# molecule-io.net
KiCad netlist of a schematic drawn in EAGLE
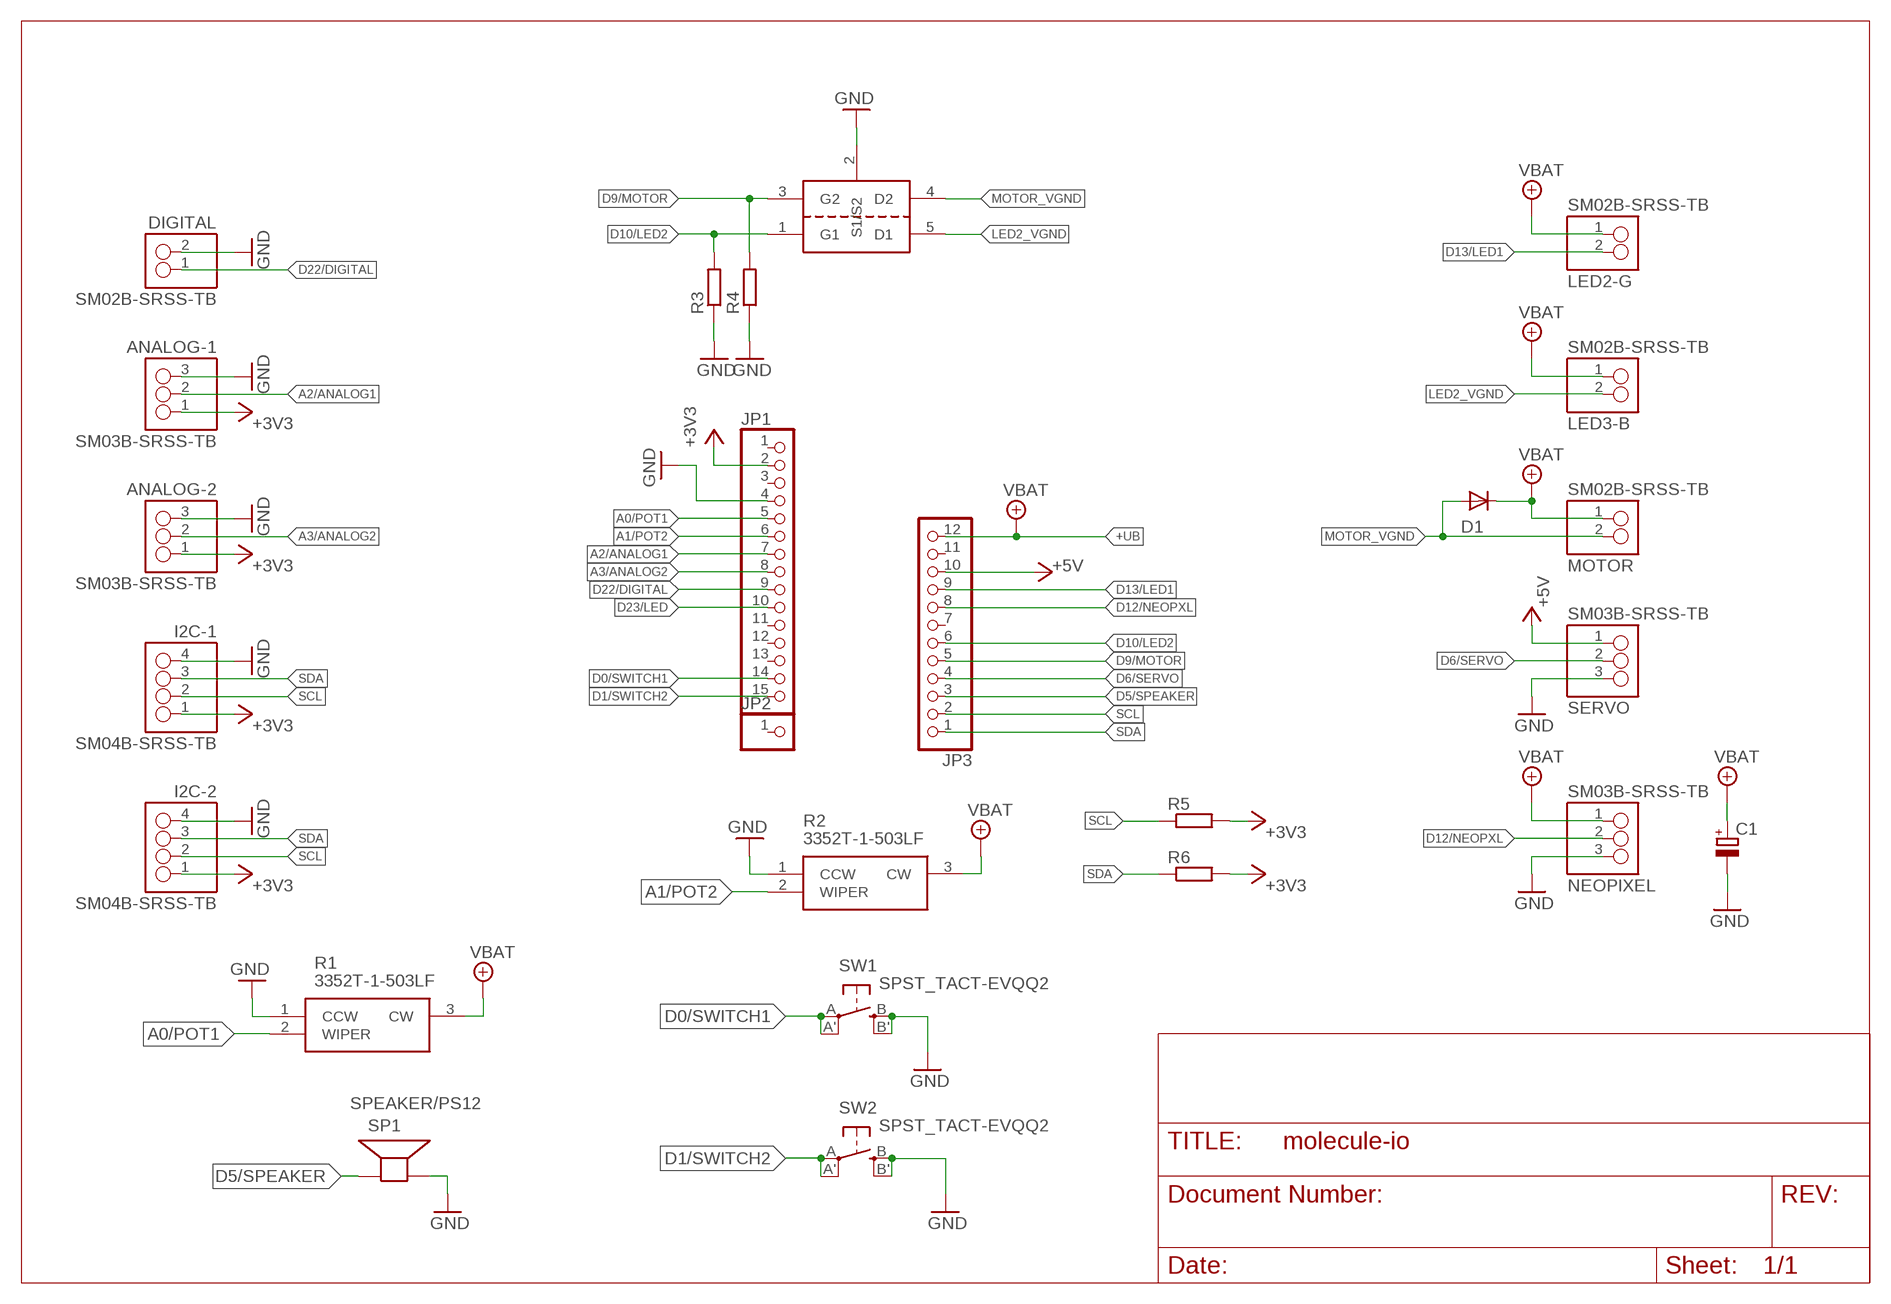
[diagram p0: schematic, sheet 1]

(export (version "E")
  (design (tool "Eeschema 10.0.6"))
  (components
    (comp (ref "ANALOG-1")
      (value "SM03B-SRSS-TB")
      (footprint "eagle-import:SM03B-SRSS-TB")
      (libsource (lib "eagle-import") (part "SM03B-SRSS-TB"))
    )
    (comp (ref "ANALOG-2")
      (value "SM03B-SRSS-TB")
      (footprint "eagle-import:SM03B-SRSS-TB")
      (libsource (lib "eagle-import") (part "SM03B-SRSS-TB"))
    )
    (comp (ref "C1")
      (value "CPOL-EUD")
      (footprint "eagle-import:PANASONIC_D")
      (libsource (lib "eagle-import") (part "CPOL-EUD"))
    )
    (comp (ref "D1")
      (value "DIODE-DO-214AC")
      (footprint "eagle-import:DO-214AC")
      (libsource (lib "eagle-import") (part "DIODE-DO-214AC"))
    )
    (comp (ref "DIGITAL")
      (value "SM02B-SRSS-TB")
      (footprint "eagle-import:SM02B-SRSS-TB")
      (libsource (lib "eagle-import") (part "SM02B-SRSS-TB"))
    )
    (comp (ref "I2C-1")
      (value "SM04B-SRSS-TB")
      (footprint "eagle-import:SM04B-SRSS-TB")
      (libsource (lib "eagle-import") (part "SM04B-SRSS-TB"))
    )
    (comp (ref "I2C-2")
      (value "SM04B-SRSS-TB")
      (footprint "eagle-import:SM04B-SRSS-TB")
      (libsource (lib "eagle-import") (part "SM04B-SRSS-TB"))
    )
    (comp (ref "JP1")
      (value "PINHD-1X15-CB")
      (footprint "eagle-import:1X15-CB")
      (libsource (lib "eagle-import") (part "PINHD-1X15-CB"))
    )
    (comp (ref "JP2")
      (value "PINHD-1X1CB")
      (footprint "eagle-import:1X01-CLEANBIG")
      (libsource (lib "eagle-import") (part "PINHD-1X1CB"))
    )
    (comp (ref "JP3")
      (value "PINHD-1X12-CB")
      (footprint "eagle-import:1X12-CB")
      (libsource (lib "eagle-import") (part "PINHD-1X12-CB"))
    )
    (comp (ref "LED2-G")
      (value "SM02B-SRSS-TB")
      (footprint "eagle-import:SM02B-SRSS-TB")
      (libsource (lib "eagle-import") (part "SM02B-SRSS-TB"))
    )
    (comp (ref "LED3-B")
      (value "SM02B-SRSS-TB")
      (footprint "eagle-import:SM02B-SRSS-TB")
      (libsource (lib "eagle-import") (part "SM02B-SRSS-TB"))
    )
    (comp (ref "MOTOR")
      (value "SM02B-SRSS-TB")
      (footprint "eagle-import:SM02B-SRSS-TB")
      (libsource (lib "eagle-import") (part "SM02B-SRSS-TB"))
    )
    (comp (ref "NEOPIXEL")
      (value "SM03B-SRSS-TB")
      (footprint "eagle-import:SM03B-SRSS-TB")
      (libsource (lib "eagle-import") (part "SM03B-SRSS-TB"))
    )
    (comp (ref "R1")
      (value "3352T-1-503LF")
      (footprint "eagle-import:3352T")
      (libsource (lib "eagle-import") (part "3352T-1-503LF"))
    )
    (comp (ref "R2")
      (value "3352T-1-503LF")
      (footprint "eagle-import:3352T")
      (libsource (lib "eagle-import") (part "3352T-1-503LF"))
    )
    (comp (ref "R3")
      (value "R-EU_R0603")
      (footprint "eagle-import:R0603")
      (libsource (lib "eagle-import") (part "R-EU_R0603"))
    )
    (comp (ref "R4")
      (value "R-EU_R0603")
      (footprint "eagle-import:R0603")
      (libsource (lib "eagle-import") (part "R-EU_R0603"))
    )
    (comp (ref "R5")
      (value "R-EU_R0603")
      (footprint "eagle-import:R0603")
      (libsource (lib "eagle-import") (part "R-EU_R0603"))
    )
    (comp (ref "R6")
      (value "R-EU_R0603")
      (footprint "eagle-import:R0603")
      (libsource (lib "eagle-import") (part "R-EU_R0603"))
    )
    (comp (ref "SERVO")
      (value "SM03B-SRSS-TB")
      (footprint "eagle-import:SM03B-SRSS-TB")
      (libsource (lib "eagle-import") (part "SM03B-SRSS-TB"))
    )
    (comp (ref "SP1")
      (value "SPEAKER/PS12")
      (footprint "eagle-import:PS12")
      (libsource (lib "eagle-import") (part "SPEAKER/PS12"))
    )
    (comp (ref "SW1")
      (value "SPST_TACT-EVQQ2")
      (footprint "eagle-import:EVQ-Q2")
      (libsource (lib "eagle-import") (part "SPST_TACT-EVQQ2"))
    )
    (comp (ref "SW2")
      (value "SPST_TACT-EVQQ2")
      (footprint "eagle-import:EVQ-Q2")
      (libsource (lib "eagle-import") (part "SPST_TACT-EVQQ2"))
    )
    (comp (ref "U1")
      (value "QS5K2")
      (footprint "eagle-import:SOT23-5L")
      (libsource (lib "eagle-import") (part "QS5K2"))
    )
  )
  (nets
    (net (code "1") (name "+3V3") (class "Default")
      (node (ref "ANALOG-1") (pin "1") (pinfunction "1_1") (pintype "bidirectional"))
      (node (ref "ANALOG-2") (pin "1") (pinfunction "1_1") (pintype "bidirectional"))
      (node (ref "I2C-1") (pin "1") (pinfunction "1_1") (pintype "bidirectional"))
      (node (ref "I2C-2") (pin "1") (pinfunction "1_1") (pintype "bidirectional"))
      (node (ref "JP1") (pin "2") (pinfunction "2_2") (pintype "passive"))
      (node (ref "R5") (pin "2") (pinfunction "2_2") (pintype "passive"))
      (node (ref "R6") (pin "2") (pinfunction "2_2") (pintype "passive"))
    )
    (net (code "2") (name "+5V") (class "Default")
      (node (ref "JP3") (pin "10") (pinfunction "10_10") (pintype "passive"))
      (node (ref "SERVO") (pin "1") (pinfunction "1_1") (pintype "bidirectional"))
    )
    (net (code "3") (name "+UB") (class "Default")
      (node (ref "C1") (pin "+") (pinfunction "+_+") (pintype "passive"))
      (node (ref "D1") (pin "C") (pinfunction "C_C") (pintype "passive"))
      (node (ref "JP3") (pin "12") (pinfunction "12_12") (pintype "passive"))
      (node (ref "LED2-G") (pin "1") (pinfunction "1_1") (pintype "bidirectional"))
      (node (ref "LED3-B") (pin "1") (pinfunction "1_1") (pintype "bidirectional"))
      (node (ref "MOTOR") (pin "1") (pinfunction "1_1") (pintype "bidirectional"))
      (node (ref "NEOPIXEL") (pin "1") (pinfunction "1_1") (pintype "bidirectional"))
      (node (ref "R1") (pin "3") (pinfunction "CW_3") (pintype "bidirectional"))
      (node (ref "R2") (pin "3") (pinfunction "CW_3") (pintype "bidirectional"))
    )
    (net (code "4") (name "A0{slash}POT1") (class "Default")
      (node (ref "JP1") (pin "5") (pinfunction "5_5") (pintype "passive"))
      (node (ref "R1") (pin "2") (pinfunction "WIPER_2") (pintype "bidirectional"))
    )
    (net (code "5") (name "A1{slash}POT2") (class "Default")
      (node (ref "JP1") (pin "6") (pinfunction "6_6") (pintype "passive"))
      (node (ref "R2") (pin "2") (pinfunction "WIPER_2") (pintype "bidirectional"))
    )
    (net (code "6") (name "A2{slash}ANALOG1") (class "Default")
      (node (ref "ANALOG-1") (pin "2") (pinfunction "2_2") (pintype "bidirectional"))
      (node (ref "JP1") (pin "7") (pinfunction "7_7") (pintype "passive"))
    )
    (net (code "7") (name "A3{slash}ANALOG2") (class "Default")
      (node (ref "ANALOG-2") (pin "2") (pinfunction "2_2") (pintype "bidirectional"))
      (node (ref "JP1") (pin "8") (pinfunction "8_8") (pintype "passive"))
    )
    (net (code "8") (name "D0{slash}SWITCH1") (class "Default")
      (node (ref "JP1") (pin "14") (pinfunction "14_14") (pintype "passive"))
      (node (ref "SW1") (pin "A") (pinfunction "P_A") (pintype "passive"))
      (node (ref "SW1") (pin "A'") (pinfunction "P1_A'") (pintype "passive"))
    )
    (net (code "9") (name "D1{slash}SWITCH2") (class "Default")
      (node (ref "JP1") (pin "15") (pinfunction "15_15") (pintype "passive"))
      (node (ref "SW2") (pin "A") (pinfunction "P_A") (pintype "passive"))
      (node (ref "SW2") (pin "A'") (pinfunction "P1_A'") (pintype "passive"))
    )
    (net (code "10") (name "D5{slash}SPEAKER") (class "Default")
      (node (ref "JP3") (pin "3") (pinfunction "3_3") (pintype "passive"))
      (node (ref "SP1") (pin "P$1") (pinfunction "+_P$1") (pintype "passive"))
    )
    (net (code "11") (name "D6{slash}SERVO") (class "Default")
      (node (ref "JP3") (pin "4") (pinfunction "4_4") (pintype "passive"))
      (node (ref "SERVO") (pin "2") (pinfunction "2_2") (pintype "bidirectional"))
    )
    (net (code "12") (name "D9{slash}MOTOR") (class "Default")
      (node (ref "JP3") (pin "5") (pinfunction "5_5") (pintype "passive"))
      (node (ref "R4") (pin "2") (pinfunction "2_2") (pintype "passive"))
      (node (ref "U1") (pin "3") (pinfunction "G2_3") (pintype "bidirectional"))
    )
    (net (code "13") (name "D10{slash}LED2") (class "Default")
      (node (ref "JP3") (pin "6") (pinfunction "6_6") (pintype "passive"))
      (node (ref "R3") (pin "2") (pinfunction "2_2") (pintype "passive"))
      (node (ref "U1") (pin "1") (pinfunction "G1_1") (pintype "bidirectional"))
    )
    (net (code "14") (name "D12{slash}NEOPXL") (class "Default")
      (node (ref "JP3") (pin "8") (pinfunction "8_8") (pintype "passive"))
      (node (ref "NEOPIXEL") (pin "2") (pinfunction "2_2") (pintype "bidirectional"))
    )
    (net (code "15") (name "D13{slash}LED1") (class "Default")
      (node (ref "JP3") (pin "9") (pinfunction "9_9") (pintype "passive"))
      (node (ref "LED2-G") (pin "2") (pinfunction "2_2") (pintype "bidirectional"))
    )
    (net (code "16") (name "D22{slash}DIGITAL") (class "Default")
      (node (ref "DIGITAL") (pin "1") (pinfunction "1_1") (pintype "bidirectional"))
      (node (ref "JP1") (pin "9") (pinfunction "9_9") (pintype "passive"))
    )
    (net (code "17") (name "D23{slash}LED") (class "Default")
      (node (ref "JP1") (pin "10") (pinfunction "10_10") (pintype "passive"))
    )
    (net (code "18") (name "GND") (class "Default")
      (node (ref "ANALOG-1") (pin "3") (pinfunction "3_3") (pintype "bidirectional"))
      (node (ref "ANALOG-2") (pin "3") (pinfunction "3_3") (pintype "bidirectional"))
      (node (ref "C1") (pin "-") (pinfunction "-_-") (pintype "passive"))
      (node (ref "DIGITAL") (pin "2") (pinfunction "2_2") (pintype "bidirectional"))
      (node (ref "I2C-1") (pin "4") (pinfunction "4_4") (pintype "bidirectional"))
      (node (ref "I2C-2") (pin "4") (pinfunction "4_4") (pintype "bidirectional"))
      (node (ref "JP1") (pin "4") (pinfunction "4_4") (pintype "passive"))
      (node (ref "NEOPIXEL") (pin "3") (pinfunction "3_3") (pintype "bidirectional"))
      (node (ref "R1") (pin "1") (pinfunction "CCW_1") (pintype "bidirectional"))
      (node (ref "R2") (pin "1") (pinfunction "CCW_1") (pintype "bidirectional"))
      (node (ref "R3") (pin "1") (pinfunction "1_1") (pintype "passive"))
      (node (ref "R4") (pin "1") (pinfunction "1_1") (pintype "passive"))
      (node (ref "SERVO") (pin "3") (pinfunction "3_3") (pintype "bidirectional"))
      (node (ref "SP1") (pin "P$2") (pinfunction "-_P$2") (pintype "passive"))
      (node (ref "SW1") (pin "B") (pinfunction "S_B") (pintype "passive"))
      (node (ref "SW1") (pin "B'") (pinfunction "S1_B'") (pintype "passive"))
      (node (ref "SW2") (pin "B") (pinfunction "S_B") (pintype "passive"))
      (node (ref "SW2") (pin "B'") (pinfunction "S1_B'") (pintype "passive"))
      (node (ref "U1") (pin "2") (pinfunction "S1/S2_2") (pintype "bidirectional"))
    )
    (net (code "19") (name "LED2_VGND") (class "Default")
      (node (ref "LED3-B") (pin "2") (pinfunction "2_2") (pintype "bidirectional"))
      (node (ref "U1") (pin "5") (pinfunction "D1_5") (pintype "bidirectional"))
    )
    (net (code "20") (name "MOTOR_VGND") (class "Default")
      (node (ref "D1") (pin "A") (pinfunction "A_A") (pintype "passive"))
      (node (ref "MOTOR") (pin "2") (pinfunction "2_2") (pintype "bidirectional"))
      (node (ref "U1") (pin "4") (pinfunction "D2_4") (pintype "bidirectional"))
    )
    (net (code "21") (name "SCL") (class "Default")
      (node (ref "I2C-1") (pin "2") (pinfunction "2_2") (pintype "bidirectional"))
      (node (ref "I2C-2") (pin "2") (pinfunction "2_2") (pintype "bidirectional"))
      (node (ref "JP3") (pin "2") (pinfunction "2_2") (pintype "passive"))
      (node (ref "R5") (pin "1") (pinfunction "1_1") (pintype "passive"))
    )
    (net (code "22") (name "SDA") (class "Default")
      (node (ref "I2C-1") (pin "3") (pinfunction "3_3") (pintype "bidirectional"))
      (node (ref "I2C-2") (pin "3") (pinfunction "3_3") (pintype "bidirectional"))
      (node (ref "JP3") (pin "1") (pinfunction "1_1") (pintype "passive"))
      (node (ref "R6") (pin "1") (pinfunction "1_1") (pintype "passive"))
    )
    (net (code "23") (name "unconnected-(JP1-Pad1)") (class "Default")
      (node (ref "JP1") (pin "1") (pinfunction "1_1") (pintype "passive"))
    )
    (net (code "24") (name "unconnected-(JP1-Pad3)") (class "Default")
      (node (ref "JP1") (pin "3") (pinfunction "3_3") (pintype "passive"))
    )
    (net (code "25") (name "unconnected-(JP1-Pad11)") (class "Default")
      (node (ref "JP1") (pin "11") (pinfunction "11_11") (pintype "passive"))
    )
    (net (code "26") (name "unconnected-(JP1-Pad12)") (class "Default")
      (node (ref "JP1") (pin "12") (pinfunction "12_12") (pintype "passive"))
    )
    (net (code "27") (name "unconnected-(JP1-Pad13)") (class "Default")
      (node (ref "JP1") (pin "13") (pinfunction "13_13") (pintype "passive"))
    )
    (net (code "28") (name "unconnected-(JP2-Pad1)") (class "Default")
      (node (ref "JP2") (pin "1") (pinfunction "1_1") (pintype "passive"))
    )
    (net (code "29") (name "unconnected-(JP3-Pad7)") (class "Default")
      (node (ref "JP3") (pin "7") (pinfunction "7_7") (pintype "passive"))
    )
    (net (code "30") (name "unconnected-(JP3-Pad11)") (class "Default")
      (node (ref "JP3") (pin "11") (pinfunction "11_11") (pintype "passive"))
    )
  )
)
